# topboard.net
KiCad netlist of a schematic drawn in EAGLE
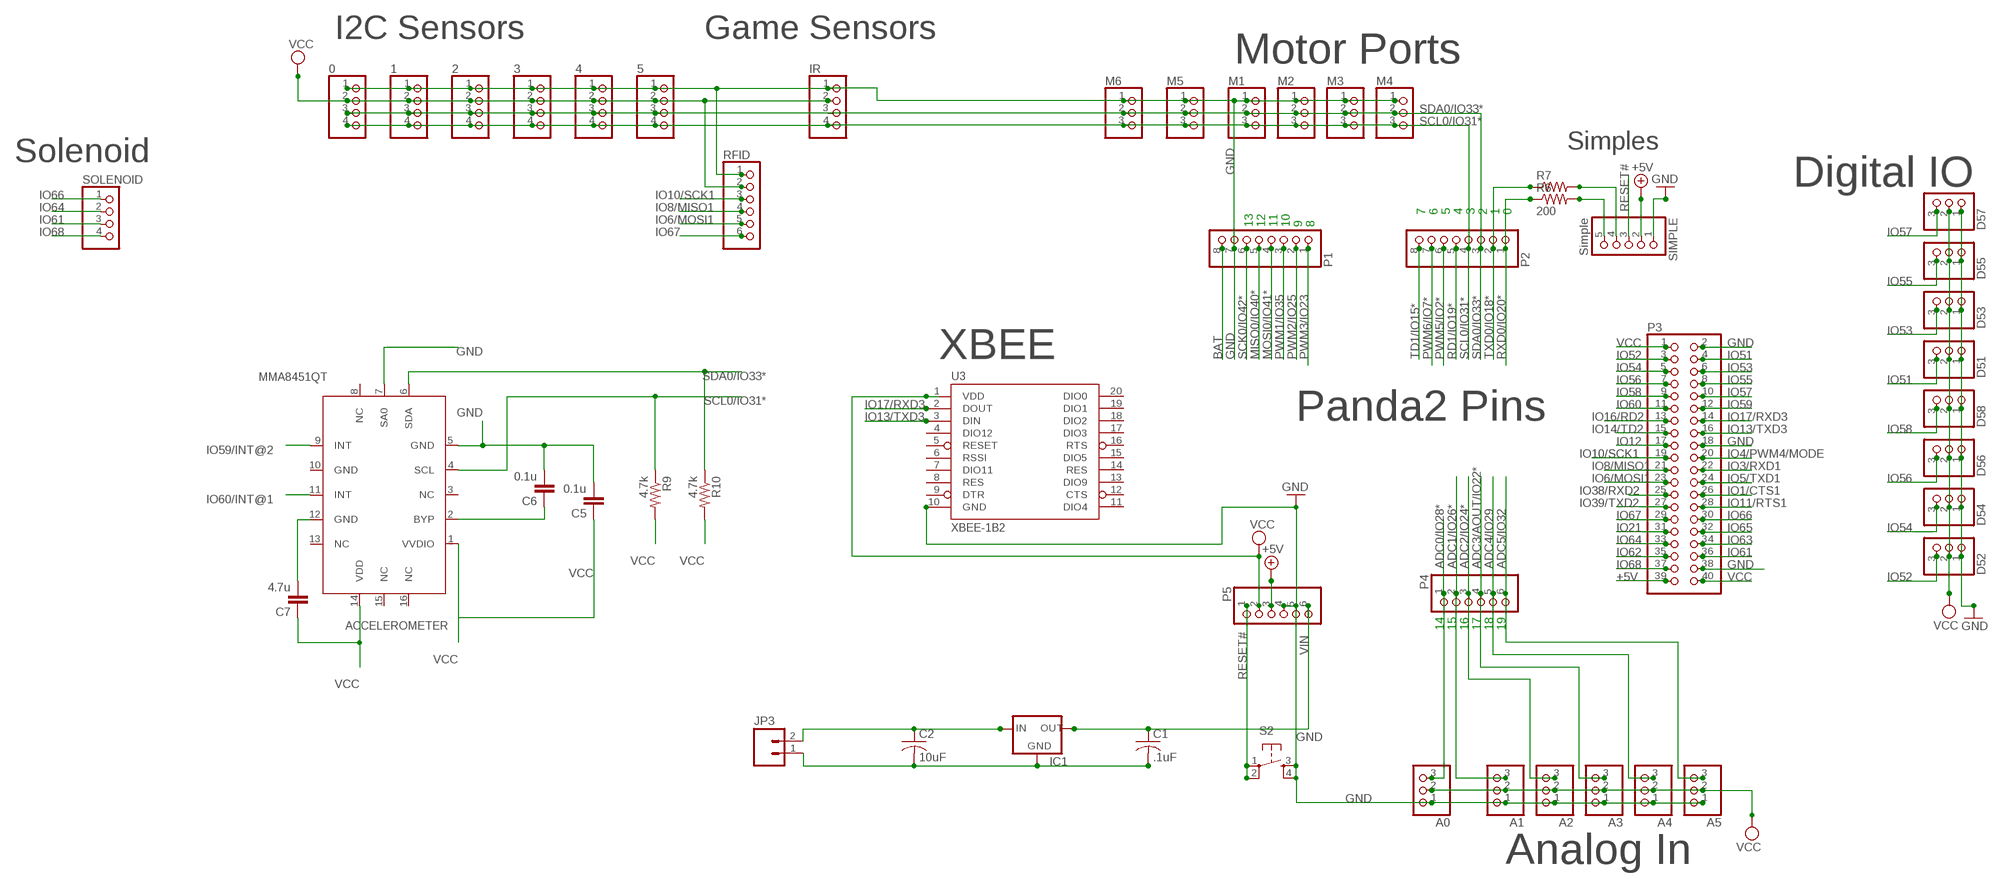
[diagram p0: schematic, sheet 1, part 1 of 2]
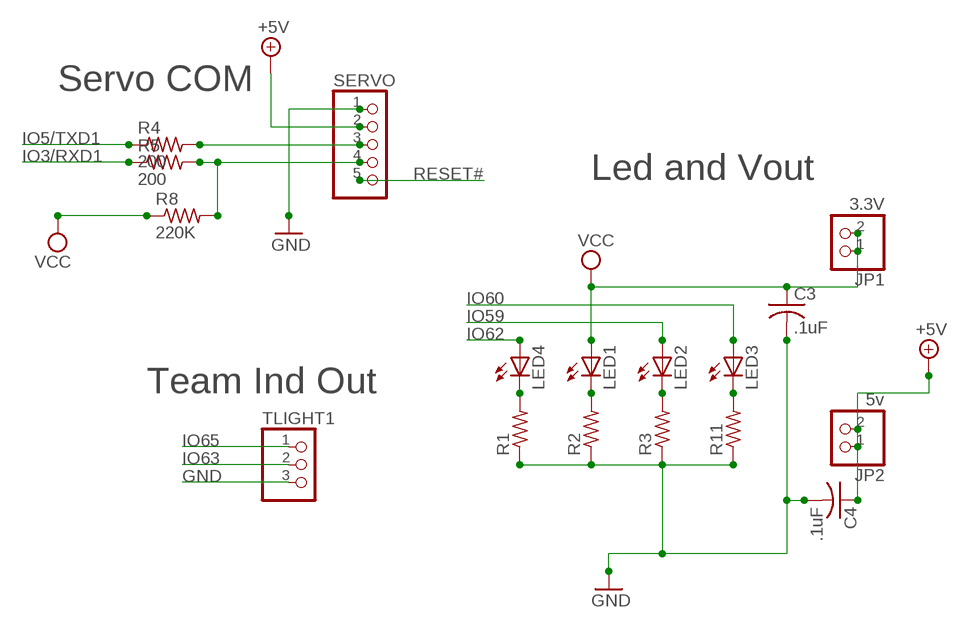
[diagram p1: schematic, sheet 1, part 2 of 2]

(export (version "E")
  (design (tool "Eeschema 10.0.6"))
  (components
    (comp (ref "0")
      (value "PINHD-1X04_2.54-S")
      (footprint "eagle-import:1X04-S")
      (libsource (lib "eagle-import") (part "PINHD-1X04_2.54-S"))
    )
    (comp (ref "1")
      (value "PINHD-1X04_2.54-S")
      (footprint "eagle-import:1X04-S")
      (libsource (lib "eagle-import") (part "PINHD-1X04_2.54-S"))
    )
    (comp (ref "2")
      (value "PINHD-1X04_2.54-S")
      (footprint "eagle-import:1X04-S")
      (libsource (lib "eagle-import") (part "PINHD-1X04_2.54-S"))
    )
    (comp (ref "3")
      (value "PINHD-1X04_2.54-S")
      (footprint "eagle-import:1X04-S")
      (libsource (lib "eagle-import") (part "PINHD-1X04_2.54-S"))
    )
    (comp (ref "4")
      (value "PINHD-1X04_2.54-S")
      (footprint "eagle-import:1X04-S")
      (libsource (lib "eagle-import") (part "PINHD-1X04_2.54-S"))
    )
    (comp (ref "5")
      (value "PINHD-1X04_2.54-S")
      (footprint "eagle-import:1X04-S")
      (libsource (lib "eagle-import") (part "PINHD-1X04_2.54-S"))
    )
    (comp (ref "A0")
      (value "PINHD-1X03_2.54-S")
      (footprint "eagle-import:1X03-S")
      (libsource (lib "eagle-import") (part "PINHD-1X03_2.54-S"))
    )
    (comp (ref "A1")
      (value "PINHD-1X03_2.54-S")
      (footprint "eagle-import:1X03-S")
      (libsource (lib "eagle-import") (part "PINHD-1X03_2.54-S"))
    )
    (comp (ref "A2")
      (value "PINHD-1X03_2.54-S")
      (footprint "eagle-import:1X03-S")
      (libsource (lib "eagle-import") (part "PINHD-1X03_2.54-S"))
    )
    (comp (ref "A3")
      (value "PINHD-1X03_2.54-S")
      (footprint "eagle-import:1X03-S")
      (libsource (lib "eagle-import") (part "PINHD-1X03_2.54-S"))
    )
    (comp (ref "A4")
      (value "PINHD-1X03_2.54-S")
      (footprint "eagle-import:1X03-S")
      (libsource (lib "eagle-import") (part "PINHD-1X03_2.54-S"))
    )
    (comp (ref "A5")
      (value "PINHD-1X03_2.54-S")
      (footprint "eagle-import:1X03-S")
      (libsource (lib "eagle-import") (part "PINHD-1X03_2.54-S"))
    )
    (comp (ref "ACCELEROMETER")
      (value "MMA8451QT")
      (footprint "eagle-import:MMA8451QT")
      (libsource (lib "eagle-import") (part "MMA8451QT"))
    )
    (comp (ref "C1")
      (value ".1uF")
      (footprint "eagle-import:C0603")
      (libsource (lib "eagle-import") (part "C-USC0603"))
    )
    (comp (ref "C2")
      (value "10uF")
      (footprint "eagle-import:C0805")
      (libsource (lib "eagle-import") (part "C-USC0805"))
    )
    (comp (ref "C3")
      (value ".1uF")
      (footprint "eagle-import:C0603K")
      (libsource (lib "eagle-import") (part "C-USC0603K"))
    )
    (comp (ref "C4")
      (value ".1uF")
      (footprint "eagle-import:C0603K")
      (libsource (lib "eagle-import") (part "C-USC0603K"))
    )
    (comp (ref "C5")
      (value "0.1u")
      (footprint "eagle-import:0603-CAP")
      (libsource (lib "eagle-import") (part "CAP0603-CAP"))
    )
    (comp (ref "C6")
      (value "0.1u")
      (footprint "eagle-import:0603-CAP")
      (libsource (lib "eagle-import") (part "CAP0603-CAP"))
    )
    (comp (ref "C7")
      (value "4.7u")
      (footprint "eagle-import:0603-CAP")
      (libsource (lib "eagle-import") (part "CAP0603-CAP"))
    )
    (comp (ref "D51")
      (value "PINHD-1X03_2.54-S")
      (footprint "eagle-import:1X03-S")
      (libsource (lib "eagle-import") (part "PINHD-1X03_2.54-S"))
    )
    (comp (ref "D52")
      (value "PINHD-1X03_2.54-S")
      (footprint "eagle-import:1X03-S")
      (libsource (lib "eagle-import") (part "PINHD-1X03_2.54-S"))
    )
    (comp (ref "D53")
      (value "PINHD-1X03_2.54-S")
      (footprint "eagle-import:1X03-S")
      (libsource (lib "eagle-import") (part "PINHD-1X03_2.54-S"))
    )
    (comp (ref "D54")
      (value "PINHD-1X03_2.54-S")
      (footprint "eagle-import:1X03-S")
      (libsource (lib "eagle-import") (part "PINHD-1X03_2.54-S"))
    )
    (comp (ref "D55")
      (value "PINHD-1X03_2.54-S")
      (footprint "eagle-import:1X03-S")
      (libsource (lib "eagle-import") (part "PINHD-1X03_2.54-S"))
    )
    (comp (ref "D56")
      (value "PINHD-1X03_2.54-S")
      (footprint "eagle-import:1X03-S")
      (libsource (lib "eagle-import") (part "PINHD-1X03_2.54-S"))
    )
    (comp (ref "D57")
      (value "PINHD-1X03_2.54-S")
      (footprint "eagle-import:1X03-S")
      (libsource (lib "eagle-import") (part "PINHD-1X03_2.54-S"))
    )
    (comp (ref "D58")
      (value "PINHD-1X03_2.54-S")
      (footprint "eagle-import:1X03-S")
      (libsource (lib "eagle-import") (part "PINHD-1X03_2.54-S"))
    )
    (comp (ref "IC1")
      (value "V_REG_78XXSIDE")
      (footprint "eagle-import:78XXL")
      (libsource (lib "eagle-import") (part "V_REG_78XXSIDE"))
    )
    (comp (ref "IR")
      (value "PINHD-1X04_2.54-S")
      (footprint "eagle-import:1X04-S")
      (libsource (lib "eagle-import") (part "PINHD-1X04_2.54-S"))
    )
    (comp (ref "JP1")
      (value "3.3V")
      (footprint "eagle-import:1X02")
      (libsource (lib "eagle-import") (part "PINHD-1X2"))
    )
    (comp (ref "JP2")
      (value "5v")
      (footprint "eagle-import:1X02")
      (libsource (lib "eagle-import") (part "PINHD-1X2"))
    )
    (comp (ref "JP3")
      (value "M02PTH4")
      (footprint "eagle-import:1X02_XTRA_BIG")
      (libsource (lib "eagle-import") (part "M02PTH4"))
    )
    (comp (ref "LED1")
      (value "LED0603")
      (footprint "eagle-import:LED-0603")
      (libsource (lib "eagle-import") (part "LED0603"))
    )
    (comp (ref "LED2")
      (value "LED0603")
      (footprint "eagle-import:LED-0603")
      (libsource (lib "eagle-import") (part "LED0603"))
    )
    (comp (ref "LED3")
      (value "LED0603")
      (footprint "eagle-import:LED-0603")
      (libsource (lib "eagle-import") (part "LED0603"))
    )
    (comp (ref "LED4")
      (value "LED0603")
      (footprint "eagle-import:LED-0603")
      (libsource (lib "eagle-import") (part "LED0603"))
    )
    (comp (ref "M1")
      (value "PINHD-1X03_2.54-S")
      (footprint "eagle-import:1X03-S")
      (libsource (lib "eagle-import") (part "PINHD-1X03_2.54-S"))
    )
    (comp (ref "M2")
      (value "PINHD-1X03_2.54-S")
      (footprint "eagle-import:1X03-S")
      (libsource (lib "eagle-import") (part "PINHD-1X03_2.54-S"))
    )
    (comp (ref "M3")
      (value "PINHD-1X03_2.54-S")
      (footprint "eagle-import:1X03-S")
      (libsource (lib "eagle-import") (part "PINHD-1X03_2.54-S"))
    )
    (comp (ref "M4")
      (value "PINHD-1X03_2.54-S")
      (footprint "eagle-import:1X03-S")
      (libsource (lib "eagle-import") (part "PINHD-1X03_2.54-S"))
    )
    (comp (ref "M5")
      (value "PINHD-1X03_2.54-S")
      (footprint "eagle-import:1X03-S")
      (libsource (lib "eagle-import") (part "PINHD-1X03_2.54-S"))
    )
    (comp (ref "M6")
      (value "PINHD-1X03_2.54-S")
      (footprint "eagle-import:1X03-S")
      (libsource (lib "eagle-import") (part "PINHD-1X03_2.54-S"))
    )
    (comp (ref "P1")
      (value "PINHD-1X08_2.54-S")
      (footprint "eagle-import:1X08-S")
      (libsource (lib "eagle-import") (part "PINHD-1X08_2.54-S"))
    )
    (comp (ref "P2")
      (value "PINHD-1X08_2.54-S")
      (footprint "eagle-import:1X08-S")
      (libsource (lib "eagle-import") (part "PINHD-1X08_2.54-S"))
    )
    (comp (ref "P3")
      (value "PINHD-2X20")
      (footprint "eagle-import:2X20")
      (libsource (lib "eagle-import") (part "PINHD-2X20"))
    )
    (comp (ref "P4")
      (value "PINHD-1X06_2.54-S")
      (footprint "eagle-import:1X06-S")
      (libsource (lib "eagle-import") (part "PINHD-1X06_2.54-S"))
    )
    (comp (ref "P5")
      (value "PINHD-1X06_2.54-S")
      (footprint "eagle-import:1X06-S")
      (libsource (lib "eagle-import") (part "PINHD-1X06_2.54-S"))
    )
    (comp (ref "R1")
      (value "R-US_R0603")
      (footprint "eagle-import:R0603")
      (libsource (lib "eagle-import") (part "R-US_R0603"))
    )
    (comp (ref "R2")
      (value "R-US_R0603")
      (footprint "eagle-import:R0603")
      (libsource (lib "eagle-import") (part "R-US_R0603"))
    )
    (comp (ref "R3")
      (value "R-US_R0603")
      (footprint "eagle-import:R0603")
      (libsource (lib "eagle-import") (part "R-US_R0603"))
    )
    (comp (ref "R4")
      (value "200")
      (footprint "eagle-import:R0603")
      (libsource (lib "eagle-import") (part "R-US_R0603"))
    )
    (comp (ref "R5")
      (value "200")
      (footprint "eagle-import:R0603")
      (libsource (lib "eagle-import") (part "R-US_R0603"))
    )
    (comp (ref "R6")
      (value "200")
      (footprint "eagle-import:R0603")
      (libsource (lib "eagle-import") (part "R-US_R0603"))
    )
    (comp (ref "R7")
      (value "R-US_R0603")
      (footprint "eagle-import:R0603")
      (libsource (lib "eagle-import") (part "R-US_R0603"))
    )
    (comp (ref "R8")
      (value "220K")
      (footprint "eagle-import:R0603")
      (libsource (lib "eagle-import") (part "R-US_R0603"))
    )
    (comp (ref "R9")
      (value "4.7k")
      (footprint "eagle-import:0603-RES")
      (libsource (lib "eagle-import") (part "RESISTOR0603-RES"))
    )
    (comp (ref "R10")
      (value "4.7k")
      (footprint "eagle-import:0603-RES")
      (libsource (lib "eagle-import") (part "RESISTOR0603-RES"))
    )
    (comp (ref "R11")
      (value "R-US_R0603")
      (footprint "eagle-import:R0603")
      (libsource (lib "eagle-import") (part "R-US_R0603"))
    )
    (comp (ref "RFID")
      (value "PINHD-1X6")
      (footprint "eagle-import:1X06")
      (libsource (lib "eagle-import") (part "PINHD-1X6"))
    )
    (comp (ref "S2")
      (value "TAC_SWITCHPTH")
      (footprint "eagle-import:TACTILE-PTH")
      (libsource (lib "eagle-import") (part "TAC_SWITCHPTH"))
    )
    (comp (ref "SERVO")
      (value "PINHD-1X05_2.54-S")
      (footprint "eagle-import:1X05-S")
      (libsource (lib "eagle-import") (part "PINHD-1X05_2.54-S"))
    )
    (comp (ref "SIMPLE")
      (value "Simple")
      (footprint "eagle-import:1X05-S")
      (libsource (lib "eagle-import") (part "PINHD-1X05_2.54-S"))
    )
    (comp (ref "SOLENOID")
      (value "PINHD-1X4")
      (footprint "eagle-import:1X04")
      (libsource (lib "eagle-import") (part "PINHD-1X4"))
    )
    (comp (ref "TLIGHT1")
      (value "PINHD-1X03_2.54-S")
      (footprint "eagle-import:1X03-S")
      (libsource (lib "eagle-import") (part "PINHD-1X03_2.54-S"))
    )
    (comp (ref "U3")
      (value "XBEE-1B2")
      (footprint "eagle-import:XBEE-SILK")
      (libsource (lib "eagle-import") (part "XBEE-1B2"))
    )
  )
  (nets
    (net (code "1") (name "+5V") (class "Default")
      (node (ref "C4") (pin "1") (pinfunction "1_1") (pintype "passive"))
      (node (ref "JP2") (pin "1") (pinfunction "1_1") (pintype "passive"))
      (node (ref "JP2") (pin "2") (pinfunction "2_2") (pintype "passive"))
      (node (ref "P3") (pin "39") (pinfunction "39_39") (pintype "passive"))
      (node (ref "P5") (pin "3") (pinfunction "3_3") (pintype "passive"))
      (node (ref "SERVO") (pin "2") (pinfunction "2_2") (pintype "passive"))
      (node (ref "SIMPLE") (pin "2") (pinfunction "2_2") (pintype "passive"))
    )
    (net (code "2") (name "/ADC0{slash}IO28*") (class "Default")
      (node (ref "A0") (pin "3") (pinfunction "3_3") (pintype "passive"))
      (node (ref "P4") (pin "1") (pinfunction "1_1") (pintype "passive"))
    )
    (net (code "3") (name "/ADC1{slash}IO26*") (class "Default")
      (node (ref "A1") (pin "3") (pinfunction "3_3") (pintype "passive"))
      (node (ref "P4") (pin "2") (pinfunction "2_2") (pintype "passive"))
    )
    (net (code "4") (name "/ADC2{slash}IO24*") (class "Default")
      (node (ref "A2") (pin "3") (pinfunction "3_3") (pintype "passive"))
      (node (ref "P4") (pin "3") (pinfunction "3_3") (pintype "passive"))
    )
    (net (code "5") (name "/ADC3{slash}AOUT{slash}IO22*") (class "Default")
      (node (ref "A3") (pin "3") (pinfunction "3_3") (pintype "passive"))
      (node (ref "P4") (pin "4") (pinfunction "4_4") (pintype "passive"))
    )
    (net (code "6") (name "/ADC4{slash}IO29") (class "Default")
      (node (ref "A4") (pin "3") (pinfunction "3_3") (pintype "passive"))
      (node (ref "P4") (pin "5") (pinfunction "5_5") (pintype "passive"))
    )
    (net (code "7") (name "/ADC5{slash}IO32") (class "Default")
      (node (ref "A5") (pin "3") (pinfunction "3_3") (pintype "passive"))
      (node (ref "P4") (pin "6") (pinfunction "6_6") (pintype "passive"))
    )
    (net (code "8") (name "/BAT") (class "Default")
      (node (ref "P1") (pin "8") (pinfunction "8_8") (pintype "passive"))
    )
    (net (code "9") (name "/IO1{slash}CTS1") (class "Default")
      (node (ref "P3") (pin "26") (pinfunction "26_26") (pintype "passive"))
    )
    (net (code "10") (name "/IO3{slash}RXD1") (class "Default")
      (node (ref "P3") (pin "22") (pinfunction "22_22") (pintype "passive"))
      (node (ref "R5") (pin "1") (pinfunction "1_1") (pintype "passive"))
    )
    (net (code "11") (name "/IO4{slash}PWM4{slash}MODE") (class "Default")
      (node (ref "P3") (pin "20") (pinfunction "20_20") (pintype "passive"))
    )
    (net (code "12") (name "/IO5{slash}TXD1") (class "Default")
      (node (ref "P3") (pin "24") (pinfunction "24_24") (pintype "passive"))
      (node (ref "R4") (pin "1") (pinfunction "1_1") (pintype "passive"))
    )
    (net (code "13") (name "/IO6{slash}MOSI1") (class "Default")
      (node (ref "P3") (pin "23") (pinfunction "23_23") (pintype "passive"))
      (node (ref "RFID") (pin "5") (pinfunction "5_5") (pintype "passive"))
    )
    (net (code "14") (name "/IO8{slash}MISO1") (class "Default")
      (node (ref "P3") (pin "21") (pinfunction "21_21") (pintype "passive"))
      (node (ref "RFID") (pin "4") (pinfunction "4_4") (pintype "passive"))
    )
    (net (code "15") (name "/IO10{slash}SCK1") (class "Default")
      (node (ref "P3") (pin "19") (pinfunction "19_19") (pintype "passive"))
      (node (ref "RFID") (pin "3") (pinfunction "3_3") (pintype "passive"))
    )
    (net (code "16") (name "/IO11{slash}RTS1") (class "Default")
      (node (ref "P3") (pin "28") (pinfunction "28_28") (pintype "passive"))
    )
    (net (code "17") (name "/IO12") (class "Default")
      (node (ref "P3") (pin "17") (pinfunction "17_17") (pintype "passive"))
    )
    (net (code "18") (name "/IO13{slash}TXD3") (class "Default")
      (node (ref "P3") (pin "16") (pinfunction "16_16") (pintype "passive"))
      (node (ref "U3") (pin "3") (pinfunction "DIN_3") (pintype "input"))
    )
    (net (code "19") (name "/IO14{slash}TD2") (class "Default")
      (node (ref "P3") (pin "15") (pinfunction "15_15") (pintype "passive"))
    )
    (net (code "20") (name "/IO16{slash}RD2") (class "Default")
      (node (ref "P3") (pin "13") (pinfunction "13_13") (pintype "passive"))
    )
    (net (code "21") (name "/IO17{slash}RXD3") (class "Default")
      (node (ref "P3") (pin "14") (pinfunction "14_14") (pintype "passive"))
      (node (ref "U3") (pin "2") (pinfunction "DOUT_2") (pintype "output"))
    )
    (net (code "22") (name "/IO21") (class "Default")
      (node (ref "P3") (pin "31") (pinfunction "31_31") (pintype "passive"))
    )
    (net (code "23") (name "/IO38{slash}RXD2") (class "Default")
      (node (ref "P3") (pin "25") (pinfunction "25_25") (pintype "passive"))
    )
    (net (code "24") (name "/IO39{slash}TXD2") (class "Default")
      (node (ref "P3") (pin "27") (pinfunction "27_27") (pintype "passive"))
    )
    (net (code "25") (name "/IO51") (class "Default")
      (node (ref "D51") (pin "3") (pinfunction "3_3") (pintype "passive"))
      (node (ref "P3") (pin "4") (pinfunction "4_4") (pintype "passive"))
    )
    (net (code "26") (name "/IO52") (class "Default")
      (node (ref "D52") (pin "3") (pinfunction "3_3") (pintype "passive"))
      (node (ref "P3") (pin "3") (pinfunction "3_3") (pintype "passive"))
    )
    (net (code "27") (name "/IO53") (class "Default")
      (node (ref "D53") (pin "3") (pinfunction "3_3") (pintype "passive"))
      (node (ref "P3") (pin "6") (pinfunction "6_6") (pintype "passive"))
    )
    (net (code "28") (name "/IO54") (class "Default")
      (node (ref "D54") (pin "3") (pinfunction "3_3") (pintype "passive"))
      (node (ref "P3") (pin "5") (pinfunction "5_5") (pintype "passive"))
    )
    (net (code "29") (name "/IO55") (class "Default")
      (node (ref "D55") (pin "3") (pinfunction "3_3") (pintype "passive"))
      (node (ref "P3") (pin "8") (pinfunction "8_8") (pintype "passive"))
    )
    (net (code "30") (name "/IO56") (class "Default")
      (node (ref "D56") (pin "3") (pinfunction "3_3") (pintype "passive"))
      (node (ref "P3") (pin "7") (pinfunction "7_7") (pintype "passive"))
    )
    (net (code "31") (name "/IO57") (class "Default")
      (node (ref "D57") (pin "3") (pinfunction "3_3") (pintype "passive"))
      (node (ref "P3") (pin "10") (pinfunction "10_10") (pintype "passive"))
    )
    (net (code "32") (name "/IO58") (class "Default")
      (node (ref "D58") (pin "3") (pinfunction "3_3") (pintype "passive"))
      (node (ref "P3") (pin "9") (pinfunction "9_9") (pintype "passive"))
    )
    (net (code "33") (name "/IO59") (class "Default")
      (node (ref "LED2") (pin "A") (pinfunction "A_A") (pintype "passive"))
      (node (ref "P3") (pin "12") (pinfunction "12_12") (pintype "passive"))
    )
    (net (code "34") (name "/IO59{slash}INT@2") (class "Default")
      (node (ref "ACCELEROMETER") (pin "9") (pinfunction "INT_9") (pintype "bidirectional"))
    )
    (net (code "35") (name "/IO60") (class "Default")
      (node (ref "LED3") (pin "A") (pinfunction "A_A") (pintype "passive"))
      (node (ref "P3") (pin "11") (pinfunction "11_11") (pintype "passive"))
    )
    (net (code "36") (name "/IO60{slash}INT@1") (class "Default")
      (node (ref "ACCELEROMETER") (pin "11") (pinfunction "INT_11") (pintype "bidirectional"))
    )
    (net (code "37") (name "/IO61") (class "Default")
      (node (ref "P3") (pin "36") (pinfunction "36_36") (pintype "passive"))
      (node (ref "SOLENOID") (pin "3") (pinfunction "3_3") (pintype "passive"))
    )
    (net (code "38") (name "/IO62") (class "Default")
      (node (ref "LED4") (pin "A") (pinfunction "A_A") (pintype "passive"))
      (node (ref "P3") (pin "35") (pinfunction "35_35") (pintype "passive"))
    )
    (net (code "39") (name "/IO63") (class "Default")
      (node (ref "P3") (pin "34") (pinfunction "34_34") (pintype "passive"))
      (node (ref "TLIGHT1") (pin "2") (pinfunction "2_2") (pintype "passive"))
    )
    (net (code "40") (name "/IO64") (class "Default")
      (node (ref "P3") (pin "33") (pinfunction "33_33") (pintype "passive"))
      (node (ref "SOLENOID") (pin "2") (pinfunction "2_2") (pintype "passive"))
    )
    (net (code "41") (name "/IO65") (class "Default")
      (node (ref "P3") (pin "32") (pinfunction "32_32") (pintype "passive"))
      (node (ref "TLIGHT1") (pin "1") (pinfunction "1_1") (pintype "passive"))
    )
    (net (code "42") (name "/IO66") (class "Default")
      (node (ref "P3") (pin "30") (pinfunction "30_30") (pintype "passive"))
      (node (ref "SOLENOID") (pin "1") (pinfunction "1_1") (pintype "passive"))
    )
    (net (code "43") (name "/IO67") (class "Default")
      (node (ref "P3") (pin "29") (pinfunction "29_29") (pintype "passive"))
      (node (ref "RFID") (pin "6") (pinfunction "6_6") (pintype "passive"))
    )
    (net (code "44") (name "/IO68") (class "Default")
      (node (ref "P3") (pin "37") (pinfunction "37_37") (pintype "passive"))
      (node (ref "SOLENOID") (pin "4") (pinfunction "4_4") (pintype "passive"))
    )
    (net (code "45") (name "/MISO0{slash}IO40*") (class "Default")
      (node (ref "P1") (pin "5") (pinfunction "5_5") (pintype "passive"))
    )
    (net (code "46") (name "/MOSI0{slash}IO41*") (class "Default")
      (node (ref "P1") (pin "4") (pinfunction "4_4") (pintype "passive"))
    )
    (net (code "47") (name "/PWM1{slash}IO35") (class "Default")
      (node (ref "P1") (pin "3") (pinfunction "3_3") (pintype "passive"))
    )
    (net (code "48") (name "/PWM2{slash}IO25") (class "Default")
      (node (ref "P1") (pin "2") (pinfunction "2_2") (pintype "passive"))
    )
    (net (code "49") (name "/PWM3{slash}IO23") (class "Default")
      (node (ref "P1") (pin "1") (pinfunction "1_1") (pintype "passive"))
    )
    (net (code "50") (name "/PWM5{slash}IO2*") (class "Default")
      (node (ref "P2") (pin "6") (pinfunction "6_6") (pintype "passive"))
    )
    (net (code "51") (name "/PWM6{slash}IO7*") (class "Default")
      (node (ref "P2") (pin "7") (pinfunction "7_7") (pintype "passive"))
    )
    (net (code "52") (name "/RD1{slash}IO19*") (class "Default")
      (node (ref "P2") (pin "5") (pinfunction "5_5") (pintype "passive"))
    )
    (net (code "53") (name "/RESET#") (class "Default")
      (node (ref "P5") (pin "1") (pinfunction "1_1") (pintype "passive"))
      (node (ref "S2") (pin "1") (pinfunction "1_1") (pintype "passive"))
      (node (ref "S2") (pin "2") (pinfunction "2_2") (pintype "passive"))
      (node (ref "SERVO") (pin "5") (pinfunction "5_5") (pintype "passive"))
      (node (ref "SIMPLE") (pin "3") (pinfunction "3_3") (pintype "passive"))
    )
    (net (code "54") (name "/RXD0{slash}IO20*") (class "Default")
      (node (ref "P2") (pin "1") (pinfunction "1_1") (pintype "passive"))
      (node (ref "R6") (pin "1") (pinfunction "1_1") (pintype "passive"))
    )
    (net (code "55") (name "/SCK0{slash}IO42*") (class "Default")
      (node (ref "P1") (pin "6") (pinfunction "6_6") (pintype "passive"))
    )
    (net (code "56") (name "/SCL0{slash}IO31*") (class "Default")
      (node (ref "0") (pin "4") (pinfunction "4_4") (pintype "passive"))
      (node (ref "1") (pin "4") (pinfunction "4_4") (pintype "passive"))
      (node (ref "2") (pin "4") (pinfunction "4_4") (pintype "passive"))
      (node (ref "3") (pin "4") (pinfunction "4_4") (pintype "passive"))
      (node (ref "4") (pin "4") (pinfunction "4_4") (pintype "passive"))
      (node (ref "5") (pin "4") (pinfunction "4_4") (pintype "passive"))
      (node (ref "ACCELEROMETER") (pin "4") (pinfunction "SCL_4") (pintype "bidirectional"))
      (node (ref "IR") (pin "4") (pinfunction "4_4") (pintype "passive"))
      (node (ref "M1") (pin "3") (pinfunction "3_3") (pintype "passive"))
      (node (ref "M2") (pin "3") (pinfunction "3_3") (pintype "passive"))
      (node (ref "M3") (pin "3") (pinfunction "3_3") (pintype "passive"))
      (node (ref "M4") (pin "3") (pinfunction "3_3") (pintype "passive"))
      (node (ref "M5") (pin "3") (pinfunction "3_3") (pintype "passive"))
      (node (ref "M6") (pin "3") (pinfunction "3_3") (pintype "passive"))
      (node (ref "P2") (pin "4") (pinfunction "4_4") (pintype "passive"))
      (node (ref "R9") (pin "1") (pinfunction "1_1") (pintype "passive"))
    )
    (net (code "57") (name "/SDA0{slash}IO33*") (class "Default")
      (node (ref "0") (pin "3") (pinfunction "3_3") (pintype "passive"))
      (node (ref "1") (pin "3") (pinfunction "3_3") (pintype "passive"))
      (node (ref "2") (pin "3") (pinfunction "3_3") (pintype "passive"))
      (node (ref "3") (pin "3") (pinfunction "3_3") (pintype "passive"))
      (node (ref "4") (pin "3") (pinfunction "3_3") (pintype "passive"))
      (node (ref "5") (pin "3") (pinfunction "3_3") (pintype "passive"))
      (node (ref "ACCELEROMETER") (pin "6") (pinfunction "SDA_6") (pintype "bidirectional"))
      (node (ref "IR") (pin "3") (pinfunction "3_3") (pintype "passive"))
      (node (ref "M1") (pin "2") (pinfunction "2_2") (pintype "passive"))
      (node (ref "M2") (pin "2") (pinfunction "2_2") (pintype "passive"))
      (node (ref "M3") (pin "2") (pinfunction "2_2") (pintype "passive"))
      (node (ref "M4") (pin "2") (pinfunction "2_2") (pintype "passive"))
      (node (ref "M5") (pin "2") (pinfunction "2_2") (pintype "passive"))
      (node (ref "M6") (pin "2") (pinfunction "2_2") (pintype "passive"))
      (node (ref "P2") (pin "3") (pinfunction "3_3") (pintype "passive"))
      (node (ref "R10") (pin "1") (pinfunction "1_1") (pintype "passive"))
    )
    (net (code "58") (name "/TD1{slash}IO15*") (class "Default")
      (node (ref "P2") (pin "8") (pinfunction "8_8") (pintype "passive"))
    )
    (net (code "59") (name "/TXD0{slash}IO18*") (class "Default")
      (node (ref "P2") (pin "2") (pinfunction "2_2") (pintype "passive"))
      (node (ref "R7") (pin "1") (pinfunction "1_1") (pintype "passive"))
    )
    (net (code "60") (name "/VIN") (class "Default")
      (node (ref "C1") (pin "1") (pinfunction "1_1") (pintype "passive"))
      (node (ref "IC1") (pin "OUT") (pinfunction "OUT_OUT") (pintype "output"))
      (node (ref "P5") (pin "6") (pinfunction "6_6") (pintype "passive"))
    )
    (net (code "61") (name "GND") (class "Default")
      (node (ref "0") (pin "1") (pinfunction "1_1") (pintype "passive"))
      (node (ref "1") (pin "1") (pinfunction "1_1") (pintype "passive"))
      (node (ref "2") (pin "1") (pinfunction "1_1") (pintype "passive"))
      (node (ref "3") (pin "1") (pinfunction "1_1") (pintype "passive"))
      (node (ref "4") (pin "1") (pinfunction "1_1") (pintype "passive"))
      (node (ref "5") (pin "1") (pinfunction "1_1") (pintype "passive"))
      (node (ref "A0") (pin "1") (pinfunction "1_1") (pintype "passive"))
      (node (ref "A1") (pin "1") (pinfunction "1_1") (pintype "passive"))
      (node (ref "A2") (pin "1") (pinfunction "1_1") (pintype "passive"))
      (node (ref "A3") (pin "1") (pinfunction "1_1") (pintype "passive"))
      (node (ref "A4") (pin "1") (pinfunction "1_1") (pintype "passive"))
      (node (ref "A5") (pin "1") (pinfunction "1_1") (pintype "passive"))
      (node (ref "ACCELEROMETER") (pin "5") (pinfunction "GND_5") (pintype "bidirectional"))
      (node (ref "ACCELEROMETER") (pin "7") (pinfunction "SA0_7") (pintype "bidirectional"))
      (node (ref "C1") (pin "2") (pinfunction "2_2") (pintype "passive"))
      (node (ref "C2") (pin "2") (pinfunction "2_2") (pintype "passive"))
      (node (ref "C3") (pin "2") (pinfunction "2_2") (pintype "passive"))
      (node (ref "C4") (pin "2") (pinfunction "2_2") (pintype "passive"))
      (node (ref "C5") (pin "2") (pinfunction "2_2") (pintype "passive"))
      (node (ref "C6") (pin "2") (pinfunction "2_2") (pintype "passive"))
      (node (ref "D51") (pin "1") (pinfunction "1_1") (pintype "passive"))
      (node (ref "D52") (pin "1") (pinfunction "1_1") (pintype "passive"))
      (node (ref "D53") (pin "1") (pinfunction "1_1") (pintype "passive"))
      (node (ref "D54") (pin "1") (pinfunction "1_1") (pintype "passive"))
      (node (ref "D55") (pin "1") (pinfunction "1_1") (pintype "passive"))
      (node (ref "D56") (pin "1") (pinfunction "1_1") (pintype "passive"))
      (node (ref "D57") (pin "1") (pinfunction "1_1") (pintype "passive"))
      (node (ref "D58") (pin "1") (pinfunction "1_1") (pintype "passive"))
      (node (ref "IC1") (pin "GND") (pinfunction "GND_GND") (pintype "input"))
      (node (ref "IC1") (pin "P$1") (pinfunction "GND_P$1") (pintype "input"))
      (node (ref "IC1") (pin "P$2") (pinfunction "GND_P$2") (pintype "input"))
      (node (ref "IR") (pin "1") (pinfunction "1_1") (pintype "passive"))
      (node (ref "JP3") (pin "1") (pinfunction "1_1") (pintype "passive"))
      (node (ref "M1") (pin "1") (pinfunction "1_1") (pintype "passive"))
      (node (ref "M2") (pin "1") (pinfunction "1_1") (pintype "passive"))
      (node (ref "M3") (pin "1") (pinfunction "1_1") (pintype "passive"))
      (node (ref "M4") (pin "1") (pinfunction "1_1") (pintype "passive"))
      (node (ref "M5") (pin "1") (pinfunction "1_1") (pintype "passive"))
      (node (ref "M6") (pin "1") (pinfunction "1_1") (pintype "passive"))
      (node (ref "P1") (pin "7") (pinfunction "7_7") (pintype "passive"))
      (node (ref "P3") (pin "18") (pinfunction "18_18") (pintype "passive"))
      (node (ref "P3") (pin "2") (pinfunction "2_2") (pintype "passive"))
      (node (ref "P3") (pin "38") (pinfunction "38_38") (pintype "passive"))
      (node (ref "P5") (pin "4") (pinfunction "4_4") (pintype "passive"))
      (node (ref "P5") (pin "5") (pinfunction "5_5") (pintype "passive"))
      (node (ref "R1") (pin "1") (pinfunction "1_1") (pintype "passive"))
      (node (ref "R11") (pin "1") (pinfunction "1_1") (pintype "passive"))
      (node (ref "R2") (pin "1") (pinfunction "1_1") (pintype "passive"))
      (node (ref "R3") (pin "1") (pinfunction "1_1") (pintype "passive"))
      (node (ref "RFID") (pin "1") (pinfunction "1_1") (pintype "passive"))
      (node (ref "S2") (pin "3") (pinfunction "3_3") (pintype "passive"))
      (node (ref "S2") (pin "4") (pinfunction "4_4") (pintype "passive"))
      (node (ref "SERVO") (pin "1") (pinfunction "1_1") (pintype "passive"))
      (node (ref "SIMPLE") (pin "1") (pinfunction "1_1") (pintype "passive"))
      (node (ref "TLIGHT1") (pin "3") (pinfunction "3_3") (pintype "passive"))
      (node (ref "U3") (pin "10") (pinfunction "GND_10") (pintype "power_in"))
    )
    (net (code "62") (name "Net-(ACCELEROMETER-BYP)") (class "Default")
      (node (ref "ACCELEROMETER") (pin "2") (pinfunction "BYP_2") (pintype "bidirectional"))
      (node (ref "C6") (pin "1") (pinfunction "1_1") (pintype "passive"))
    )
    (net (code "63") (name "Net-(ACCELEROMETER-GND-Pad12)") (class "Default")
      (node (ref "ACCELEROMETER") (pin "12") (pinfunction "GND_12") (pintype "bidirectional"))
      (node (ref "C7") (pin "2") (pinfunction "2_2") (pintype "passive"))
    )
    (net (code "64") (name "Net-(C2-Pad1)") (class "Default")
      (node (ref "C2") (pin "1") (pinfunction "1_1") (pintype "passive"))
      (node (ref "IC1") (pin "IN") (pinfunction "IN_IN") (pintype "input"))
      (node (ref "JP3") (pin "2") (pinfunction "2_2") (pintype "passive"))
    )
    (net (code "65") (name "Net-(LED1-PadC)") (class "Default")
      (node (ref "LED1") (pin "C") (pinfunction "C_C") (pintype "passive"))
      (node (ref "R2") (pin "2") (pinfunction "2_2") (pintype "passive"))
    )
    (net (code "66") (name "Net-(LED2-PadC)") (class "Default")
      (node (ref "LED2") (pin "C") (pinfunction "C_C") (pintype "passive"))
      (node (ref "R3") (pin "2") (pinfunction "2_2") (pintype "passive"))
    )
    (net (code "67") (name "Net-(LED3-PadC)") (class "Default")
      (node (ref "LED3") (pin "C") (pinfunction "C_C") (pintype "passive"))
      (node (ref "R11") (pin "2") (pinfunction "2_2") (pintype "passive"))
    )
    (net (code "68") (name "Net-(LED4-PadC)") (class "Default")
      (node (ref "LED4") (pin "C") (pinfunction "C_C") (pintype "passive"))
      (node (ref "R1") (pin "2") (pinfunction "2_2") (pintype "passive"))
    )
    (net (code "69") (name "Net-(R4-Pad2)") (class "Default")
      (node (ref "R4") (pin "2") (pinfunction "2_2") (pintype "passive"))
      (node (ref "SERVO") (pin "3") (pinfunction "3_3") (pintype "passive"))
    )
    (net (code "70") (name "Net-(R5-Pad2)") (class "Default")
      (node (ref "R5") (pin "2") (pinfunction "2_2") (pintype "passive"))
      (node (ref "R8") (pin "2") (pinfunction "2_2") (pintype "passive"))
      (node (ref "SERVO") (pin "4") (pinfunction "4_4") (pintype "passive"))
    )
    (net (code "71") (name "Net-(R6-Pad2)") (class "Default")
      (node (ref "R6") (pin "2") (pinfunction "2_2") (pintype "passive"))
      (node (ref "SIMPLE") (pin "5") (pinfunction "5_5") (pintype "passive"))
    )
    (net (code "72") (name "Net-(R7-Pad2)") (class "Default")
      (node (ref "R7") (pin "2") (pinfunction "2_2") (pintype "passive"))
      (node (ref "SIMPLE") (pin "4") (pinfunction "4_4") (pintype "passive"))
    )
    (net (code "73") (name "VCC") (class "Default")
      (node (ref "0") (pin "2") (pinfunction "2_2") (pintype "passive"))
      (node (ref "1") (pin "2") (pinfunction "2_2") (pintype "passive"))
      (node (ref "2") (pin "2") (pinfunction "2_2") (pintype "passive"))
      (node (ref "3") (pin "2") (pinfunction "2_2") (pintype "passive"))
      (node (ref "4") (pin "2") (pinfunction "2_2") (pintype "passive"))
      (node (ref "5") (pin "2") (pinfunction "2_2") (pintype "passive"))
      (node (ref "A0") (pin "2") (pinfunction "2_2") (pintype "passive"))
      (node (ref "A1") (pin "2") (pinfunction "2_2") (pintype "passive"))
      (node (ref "A2") (pin "2") (pinfunction "2_2") (pintype "passive"))
      (node (ref "A3") (pin "2") (pinfunction "2_2") (pintype "passive"))
      (node (ref "A4") (pin "2") (pinfunction "2_2") (pintype "passive"))
      (node (ref "A5") (pin "2") (pinfunction "2_2") (pintype "passive"))
      (node (ref "ACCELEROMETER") (pin "1") (pinfunction "VVDIO_1") (pintype "bidirectional"))
      (node (ref "ACCELEROMETER") (pin "14") (pinfunction "VDD_14") (pintype "bidirectional"))
      (node (ref "C3") (pin "1") (pinfunction "1_1") (pintype "passive"))
      (node (ref "C5") (pin "1") (pinfunction "1_1") (pintype "passive"))
      (node (ref "C7") (pin "1") (pinfunction "1_1") (pintype "passive"))
      (node (ref "D51") (pin "2") (pinfunction "2_2") (pintype "passive"))
      (node (ref "D52") (pin "2") (pinfunction "2_2") (pintype "passive"))
      (node (ref "D53") (pin "2") (pinfunction "2_2") (pintype "passive"))
      (node (ref "D54") (pin "2") (pinfunction "2_2") (pintype "passive"))
      (node (ref "D55") (pin "2") (pinfunction "2_2") (pintype "passive"))
      (node (ref "D56") (pin "2") (pinfunction "2_2") (pintype "passive"))
      (node (ref "D57") (pin "2") (pinfunction "2_2") (pintype "passive"))
      (node (ref "D58") (pin "2") (pinfunction "2_2") (pintype "passive"))
      (node (ref "IR") (pin "2") (pinfunction "2_2") (pintype "passive"))
      (node (ref "JP1") (pin "1") (pinfunction "1_1") (pintype "passive"))
      (node (ref "JP1") (pin "2") (pinfunction "2_2") (pintype "passive"))
      (node (ref "LED1") (pin "A") (pinfunction "A_A") (pintype "passive"))
      (node (ref "P3") (pin "1") (pinfunction "1_1") (pintype "passive"))
      (node (ref "P3") (pin "40") (pinfunction "40_40") (pintype "passive"))
      (node (ref "P5") (pin "2") (pinfunction "2_2") (pintype "passive"))
      (node (ref "R10") (pin "2") (pinfunction "2_2") (pintype "passive"))
      (node (ref "R8") (pin "1") (pinfunction "1_1") (pintype "passive"))
      (node (ref "R9") (pin "2") (pinfunction "2_2") (pintype "passive"))
      (node (ref "RFID") (pin "2") (pinfunction "2_2") (pintype "passive"))
      (node (ref "U3") (pin "1") (pinfunction "VDD_1") (pintype "power_in"))
    )
    (net (code "74") (name "unconnected-(ACCELEROMETER-GND-Pad10)") (class "Default")
      (node (ref "ACCELEROMETER") (pin "10") (pinfunction "GND_10") (pintype "bidirectional"))
    )
    (net (code "75") (name "unconnected-(ACCELEROMETER-NC-Pad3)") (class "Default")
      (node (ref "ACCELEROMETER") (pin "3") (pinfunction "NC_3") (pintype "bidirectional"))
    )
    (net (code "76") (name "unconnected-(ACCELEROMETER-NC-Pad8)") (class "Default")
      (node (ref "ACCELEROMETER") (pin "8") (pinfunction "NC_8") (pintype "bidirectional"))
    )
    (net (code "77") (name "unconnected-(ACCELEROMETER-NC-Pad13)") (class "Default")
      (node (ref "ACCELEROMETER") (pin "13") (pinfunction "NC_13") (pintype "bidirectional"))
    )
    (net (code "78") (name "unconnected-(ACCELEROMETER-NC-Pad15)") (class "Default")
      (node (ref "ACCELEROMETER") (pin "15") (pinfunction "NC_15") (pintype "bidirectional"))
    )
    (net (code "79") (name "unconnected-(ACCELEROMETER-NC-Pad16)") (class "Default")
      (node (ref "ACCELEROMETER") (pin "16") (pinfunction "NC_16") (pintype "bidirectional"))
    )
    (net (code "80") (name "unconnected-(U3-CTS-Pad12)") (class "Default")
      (node (ref "U3") (pin "12") (pinfunction "CTS_12") (pintype "output"))
    )
    (net (code "81") (name "unconnected-(U3-DIO0-Pad20)") (class "Default")
      (node (ref "U3") (pin "20") (pinfunction "DIO0_20") (pintype "bidirectional"))
    )
    (net (code "82") (name "unconnected-(U3-DIO1-Pad19)") (class "Default")
      (node (ref "U3") (pin "19") (pinfunction "DIO1_19") (pintype "bidirectional"))
    )
    (net (code "83") (name "unconnected-(U3-DIO2-Pad18)") (class "Default")
      (node (ref "U3") (pin "18") (pinfunction "DIO2_18") (pintype "bidirectional"))
    )
    (net (code "84") (name "unconnected-(U3-DIO3-Pad17)") (class "Default")
      (node (ref "U3") (pin "17") (pinfunction "DIO3_17") (pintype "bidirectional"))
    )
    (net (code "85") (name "unconnected-(U3-DIO4-Pad11)") (class "Default")
      (node (ref "U3") (pin "11") (pinfunction "DIO4_11") (pintype "bidirectional"))
    )
    (net (code "86") (name "unconnected-(U3-DIO5-Pad15)") (class "Default")
      (node (ref "U3") (pin "15") (pinfunction "DIO5_15") (pintype "bidirectional"))
    )
    (net (code "87") (name "unconnected-(U3-DIO9-Pad13)") (class "Default")
      (node (ref "U3") (pin "13") (pinfunction "DIO9_13") (pintype "bidirectional"))
    )
    (net (code "88") (name "unconnected-(U3-DIO11-Pad7)") (class "Default")
      (node (ref "U3") (pin "7") (pinfunction "DIO11_7") (pintype "bidirectional"))
    )
    (net (code "89") (name "unconnected-(U3-DIO12-Pad4)") (class "Default")
      (node (ref "U3") (pin "4") (pinfunction "DIO12_4") (pintype "bidirectional"))
    )
    (net (code "90") (name "unconnected-(U3-DTR-Pad9)") (class "Default")
      (node (ref "U3") (pin "9") (pinfunction "DTR_9") (pintype "bidirectional"))
    )
    (net (code "91") (name "unconnected-(U3-RES-Pad8)") (class "Default")
      (node (ref "U3") (pin "8") (pinfunction "RES_8") (pintype "bidirectional"))
    )
    (net (code "92") (name "unconnected-(U3-RES-Pad14)") (class "Default")
      (node (ref "U3") (pin "14") (pinfunction "RES_14") (pintype "bidirectional"))
    )
    (net (code "93") (name "unconnected-(U3-RESET-Pad5)") (class "Default")
      (node (ref "U3") (pin "5") (pinfunction "RESET_5") (pintype "input"))
    )
    (net (code "94") (name "unconnected-(U3-RSSI-Pad6)") (class "Default")
      (node (ref "U3") (pin "6") (pinfunction "RSSI_6") (pintype "bidirectional"))
    )
    (net (code "95") (name "unconnected-(U3-RTS-Pad16)") (class "Default")
      (node (ref "U3") (pin "16") (pinfunction "RTS_16") (pintype "input"))
    )
  )
)
